# FPGA_SPI.net
KiCad netlist of a schematic drawn in Altium Designer
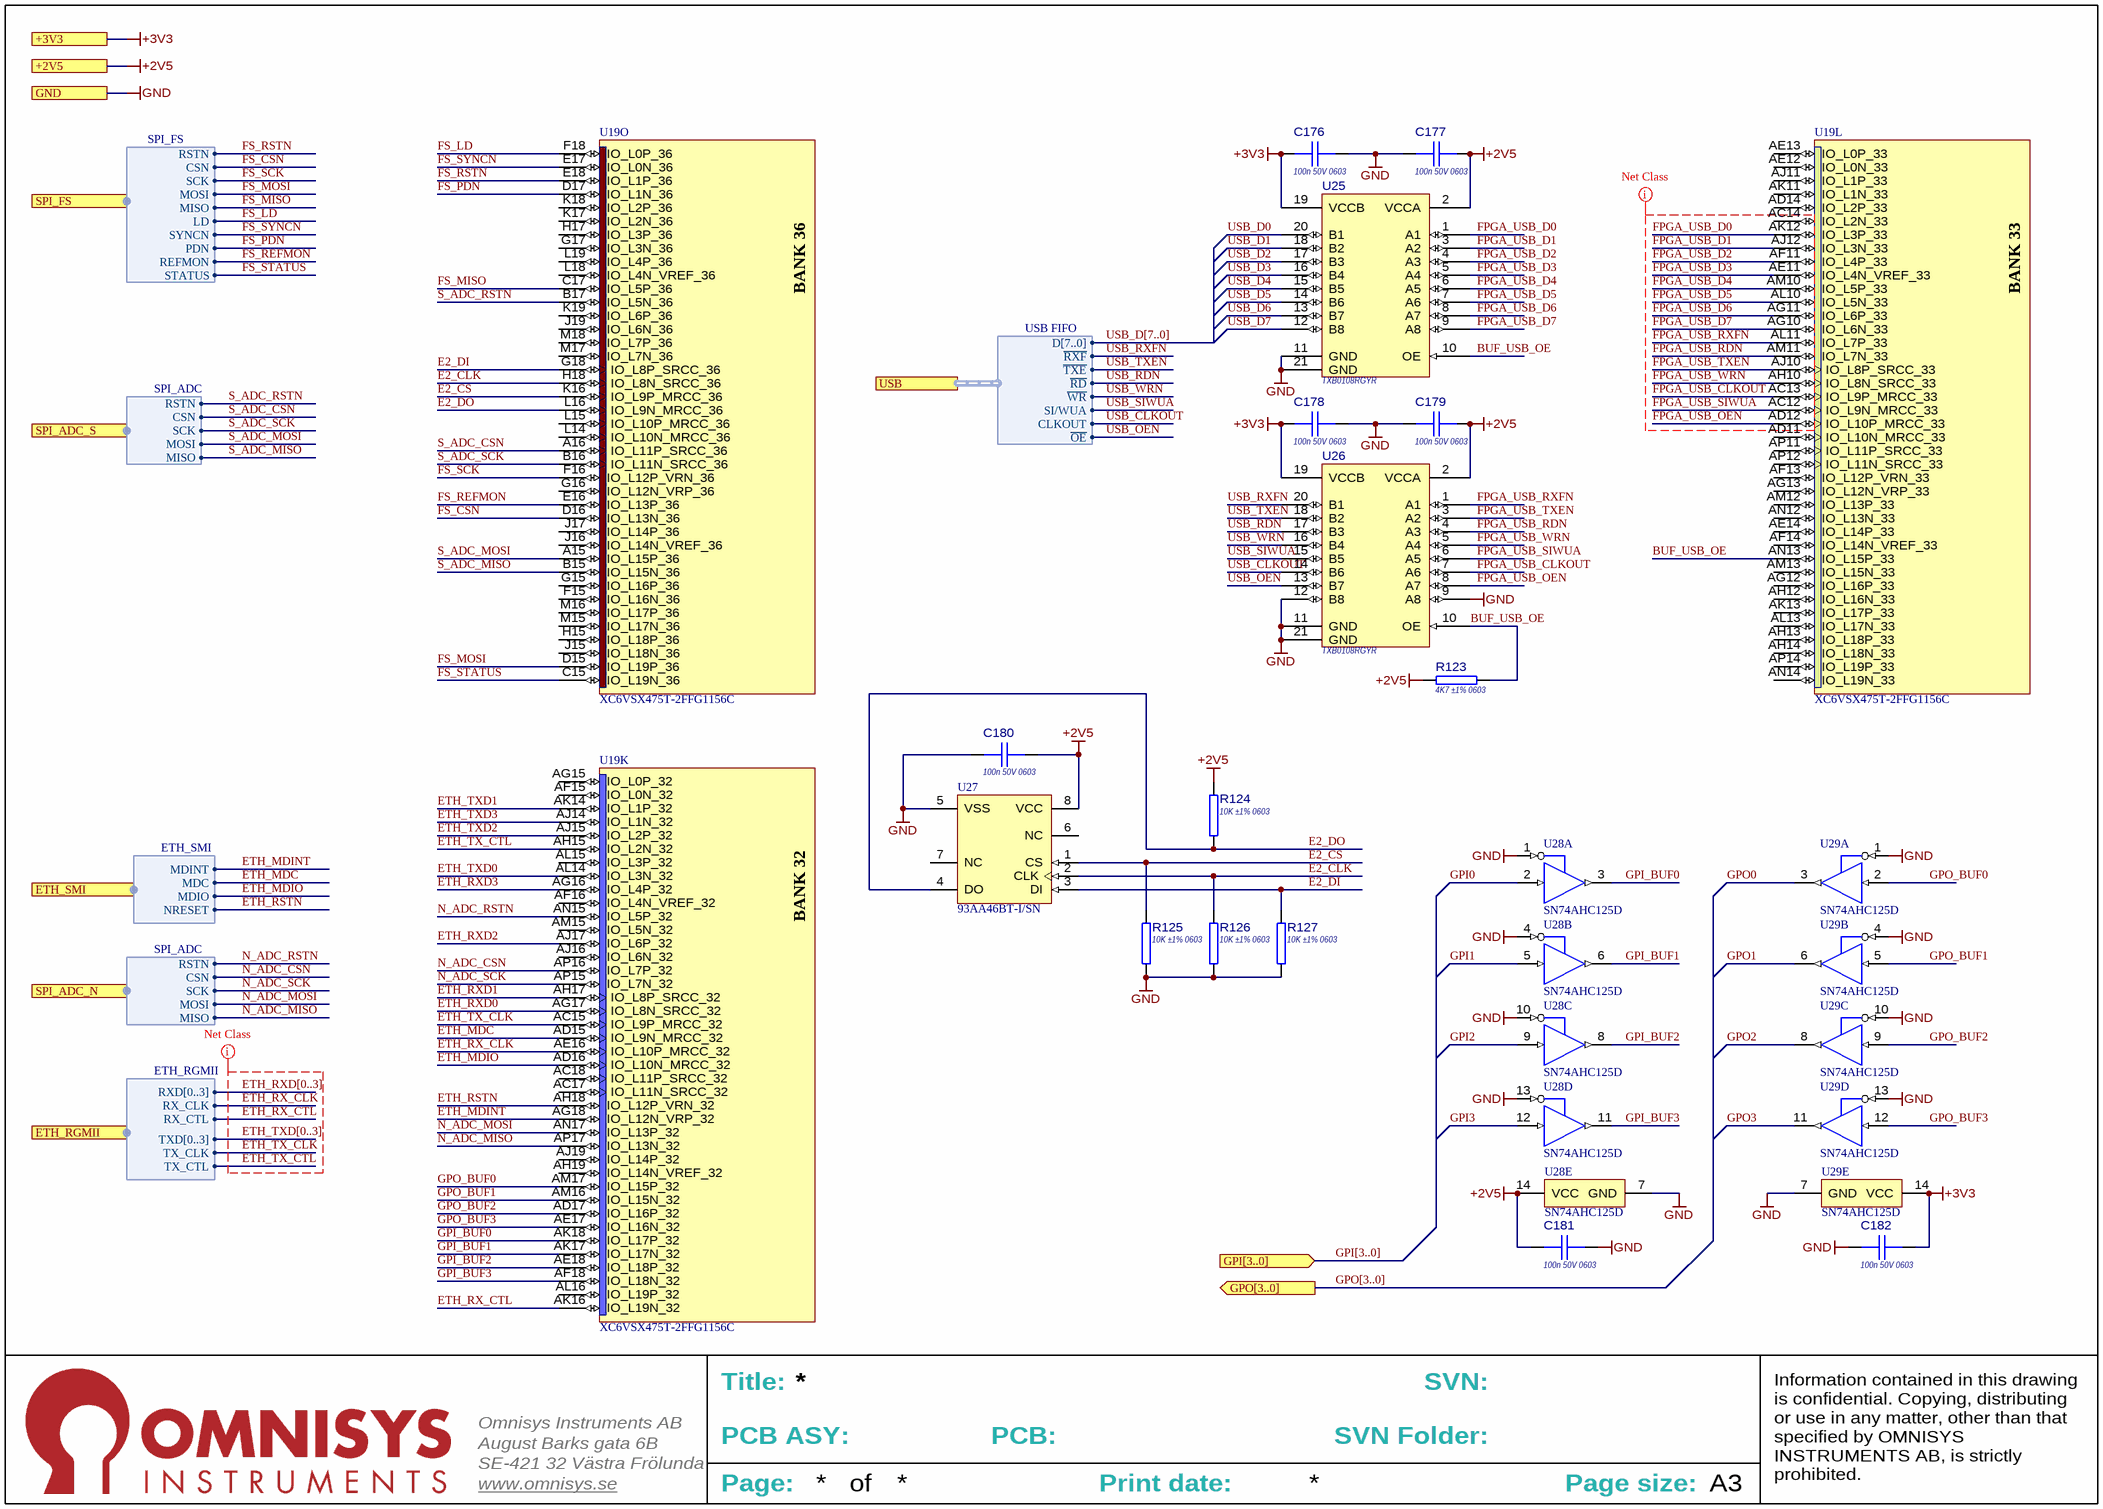
[diagram p0: FPGA_SPI.SchDoc]

(export (version "E")
  (design (tool "Eeschema 10.0.6"))
  (components
    (comp (ref "C176")
      (value "100n 50V 0603")
      (footprint "CAPC1608X90N")
      (description "100n 50V X7R ±10% 0603 (1608 metric)")
      (fields (field (name "PARTNUMBER") "GRM188R71H104KA93") (field (name "TOLERANCE") "±10%"))
      (libsource (lib "Omnisys Vault") (part "CAP-2PIN"))
    )
    (comp (ref "C177")
      (value "100n 50V 0603")
      (footprint "CAPC1608X90N")
      (description "100n 50V X7R ±10% 0603 (1608 metric)")
      (fields (field (name "PARTNUMBER") "GRM188R71H104KA93") (field (name "TOLERANCE") "±10%"))
      (libsource (lib "Omnisys Vault") (part "CAP-2PIN"))
    )
    (comp (ref "C178")
      (value "100n 50V 0603")
      (footprint "CAPC1608X90N")
      (description "100n 50V X7R ±10% 0603 (1608 metric)")
      (fields (field (name "PARTNUMBER") "GRM188R71H104KA93") (field (name "TOLERANCE") "±10%"))
      (libsource (lib "Omnisys Vault") (part "CAP-2PIN"))
    )
    (comp (ref "C179")
      (value "100n 50V 0603")
      (footprint "CAPC1608X90N")
      (description "100n 50V X7R ±10% 0603 (1608 metric)")
      (fields (field (name "PARTNUMBER") "GRM188R71H104KA93") (field (name "TOLERANCE") "±10%"))
      (libsource (lib "Omnisys Vault") (part "CAP-2PIN"))
    )
    (comp (ref "C180")
      (value "100n 50V 0603")
      (footprint "CAPC1608X90N")
      (description "100n 50V X7R ±10% 0603 (1608 metric)")
      (fields (field (name "PARTNUMBER") "GRM188R71H104KA93") (field (name "TOLERANCE") "±10%"))
      (libsource (lib "Omnisys Vault") (part "CAP-2PIN"))
    )
    (comp (ref "C181")
      (value "100n 50V 0603")
      (footprint "CAPC1608X90N")
      (description "100n 50V X7R ±10% 0603 (1608 metric)")
      (fields (field (name "PARTNUMBER") "GRM188R71H104KA93") (field (name "TOLERANCE") "±10%"))
      (libsource (lib "Omnisys Vault") (part "CAP-2PIN"))
    )
    (comp (ref "C182")
      (value "100n 50V 0603")
      (footprint "CAPC1608X90N")
      (description "100n 50V X7R ±10% 0603 (1608 metric)")
      (fields (field (name "PARTNUMBER") "GRM188R71H104KA93") (field (name "TOLERANCE") "±10%"))
      (libsource (lib "Omnisys Vault") (part "CAP-2PIN"))
    )
    (comp (ref "R123")
      (value "4K7 ±1% 0603")
      (footprint "RESC1608N")
      (description "4K7 ±1% ±100 ppm/˚C 0.10W 75V 0603 (1608 metric)")
      (fields (field (name "POWER") "100mW") (field (name "TOLERANCE") "1%"))
      (libsource (lib "Omnisys Vault") (part "RES-2PIN"))
    )
    (comp (ref "R124")
      (value "10K ±1% 0603")
      (footprint "RESC1608N")
      (description "10K ±1% ±100 ppm/˚C 0.10W 75V 0603 (1608 metric)")
      (fields (field (name "POWER") "100mW") (field (name "TOLERANCE") "1%"))
      (libsource (lib "Omnisys Vault") (part "RES-2PIN"))
    )
    (comp (ref "R125")
      (value "10K ±1% 0603")
      (footprint "RESC1608N")
      (description "10K ±1% ±100 ppm/˚C 0.10W 75V 0603 (1608 metric)")
      (fields (field (name "POWER") "100mW") (field (name "TOLERANCE") "1%"))
      (libsource (lib "Omnisys Vault") (part "RES-2PIN"))
    )
    (comp (ref "R126")
      (value "10K ±1% 0603")
      (footprint "RESC1608N")
      (description "10K ±1% ±100 ppm/˚C 0.10W 75V 0603 (1608 metric)")
      (fields (field (name "POWER") "100mW") (field (name "TOLERANCE") "1%"))
      (libsource (lib "Omnisys Vault") (part "RES-2PIN"))
    )
    (comp (ref "R127")
      (value "10K ±1% 0603")
      (footprint "RESC1608N")
      (description "10K ±1% ±100 ppm/˚C 0.10W 75V 0603 (1608 metric)")
      (fields (field (name "POWER") "100mW") (field (name "TOLERANCE") "1%"))
      (libsource (lib "Omnisys Vault") (part "RES-2PIN"))
    )
    (comp (ref "U19")
      (value "XC6VSX475T-2FFG1156C")
      (footprint "FFG1156")
      (libsource (lib "Altium Content Vault") (part "FPGA-XVR6-XC6VXXXXXT-GA1156"))
    )
    (comp (ref "U25")
      (value "TXB0108RGYR")
      (footprint "TXB0108RGYR")
      (description "TEXAS INSTRUMENTS   TXB0108RGYR   TRANSLATOR, VOLTAGE, 8BIT, 20VQFN")
      (libsource (lib "Omnisys Vault") (part "TXB0108RGYR"))
    )
    (comp (ref "U26")
      (value "TXB0108RGYR")
      (footprint "TXB0108RGYR")
      (description "TEXAS INSTRUMENTS   TXB0108RGYR   TRANSLATOR, VOLTAGE, 8BIT, 20VQFN")
      (libsource (lib "Omnisys Vault") (part "TXB0108RGYR"))
    )
    (comp (ref "U27")
      (value "93AA46BT-I/SN")
      (footprint "SOIC-SN8_L")
      (libsource (lib "Altium Content Vault") (part "MEM-SEEPROM-93AA46B-P-8"))
    )
    (comp (ref "U28")
      (value "SN74AHC125D")
      (footprint "SOIC127P600X175-14N")
      (description "Buffer/Line Driver 4-CH Non-Inverting 3-ST CMOS 14-Pin SOIC Tube")
      (libsource (lib "") (part "SN74AHC125D_1"))
    )
    (comp (ref "U29")
      (value "SN74AHC125D")
      (footprint "SOIC127P600X175-14L")
      (description "Buffer/Line Driver 4-CH Non-Inverting 3-ST CMOS 14-Pin SOIC Tube")
      (libsource (lib "Omnisys Vault") (part "SN74AHC125D"))
    )
  )
  (nets
    (net (code "7") (name "+2V5") (class "Default")
      (node (ref "C177") (pin "2") (pinfunction "2_2") (pintype "passive"))
      (node (ref "C179") (pin "2") (pinfunction "2_2") (pintype "passive"))
      (node (ref "C180") (pin "2") (pinfunction "2_2") (pintype "passive"))
      (node (ref "C181") (pin "1") (pinfunction "1_1") (pintype "passive"))
      (node (ref "R123") (pin "2") (pinfunction "2_2") (pintype "passive"))
      (node (ref "R124") (pin "2") (pinfunction "2_2") (pintype "passive"))
      (node (ref "U25") (pin "2") (pinfunction "VCCA_2") (pintype "power_in"))
      (node (ref "U26") (pin "2") (pinfunction "VCCA_2") (pintype "power_in"))
      (node (ref "U27") (pin "8") (pinfunction "VCC_8") (pintype "power_in"))
      (node (ref "U28") (pin "14") (pinfunction "VCC_14") (pintype "power_in"))
    )
    (net (code "8") (name "+3V3") (class "Default")
      (node (ref "C176") (pin "1") (pinfunction "1_1") (pintype "passive"))
      (node (ref "C178") (pin "1") (pinfunction "1_1") (pintype "passive"))
      (node (ref "C182") (pin "1") (pinfunction "1_1") (pintype "passive"))
      (node (ref "U25") (pin "19") (pinfunction "VCCB_19") (pintype "power_in"))
      (node (ref "U26") (pin "19") (pinfunction "VCCB_19") (pintype "power_in"))
      (node (ref "U29") (pin "14") (pinfunction "VCC_14") (pintype "power_in"))
    )
    (net (code "9") (name "/BUF_USB_OE") (class "Default")
      (node (ref "R123") (pin "1") (pinfunction "1_1") (pintype "passive"))
      (node (ref "U19") (pin "AN13") (pinfunction "IO_L15P_33_AN13") (pintype "bidirectional"))
      (node (ref "U25") (pin "10") (pinfunction "OE_10") (pintype "input"))
      (node (ref "U26") (pin "10") (pinfunction "OE_10") (pintype "input"))
    )
    (net (code "10") (name "/E2_CLK") (class "Default")
      (node (ref "R126") (pin "2") (pinfunction "2_2") (pintype "passive"))
      (node (ref "U19") (pin "H18") (pinfunction "IO_L8N_SRCC_36_H18") (pintype "bidirectional"))
      (node (ref "U27") (pin "2") (pinfunction "CLK_2") (pintype "input"))
    )
    (net (code "11") (name "/E2_CS") (class "Default")
      (node (ref "R125") (pin "2") (pinfunction "2_2") (pintype "passive"))
      (node (ref "U19") (pin "K16") (pinfunction "IO_L9P_MRCC_36_K16") (pintype "bidirectional"))
      (node (ref "U27") (pin "1") (pinfunction "CS_1") (pintype "input"))
    )
    (net (code "12") (name "/E2_DI") (class "Default")
      (node (ref "R127") (pin "2") (pinfunction "2_2") (pintype "passive"))
      (node (ref "U19") (pin "G18") (pinfunction "IO_L8P_SRCC_36_G18") (pintype "bidirectional"))
      (node (ref "U27") (pin "3") (pinfunction "DI_3") (pintype "input"))
    )
    (net (code "13") (name "/E2_DO") (class "Default")
      (node (ref "R124") (pin "1") (pinfunction "1_1") (pintype "passive"))
      (node (ref "U19") (pin "L16") (pinfunction "IO_L9N_MRCC_36_L16") (pintype "bidirectional"))
      (node (ref "U27") (pin "4") (pinfunction "DO_4") (pintype "tri_state"))
    )
    (net (code "14") (name "/ETH_MDC") (class "Default")
      (node (ref "U19") (pin "AD15") (pinfunction "IO_L9N_MRCC_32_AD15") (pintype "bidirectional"))
    )
    (net (code "15") (name "/ETH_MDINT") (class "Default")
      (node (ref "U19") (pin "AG18") (pinfunction "IO_L12N_VRP_32_AG18") (pintype "bidirectional"))
    )
    (net (code "16") (name "/ETH_MDIO") (class "Default")
      (node (ref "U19") (pin "AD16") (pinfunction "IO_L10N_MRCC_32_AD16") (pintype "bidirectional"))
    )
    (net (code "18") (name "/ETH_RSTN") (class "Default")
      (node (ref "U19") (pin "AH18") (pinfunction "IO_L12P_VRN_32_AH18") (pintype "bidirectional"))
    )
    (net (code "19") (name "/ETH_RXD0") (class "Default")
      (node (ref "U19") (pin "AG17") (pinfunction "IO_L8N_SRCC_32_AG17") (pintype "bidirectional"))
    )
    (net (code "20") (name "/ETH_RXD1") (class "Default")
      (node (ref "U19") (pin "AH17") (pinfunction "IO_L8P_SRCC_32_AH17") (pintype "bidirectional"))
    )
    (net (code "21") (name "/ETH_RXD2") (class "Default")
      (node (ref "U19") (pin "AJ17") (pinfunction "IO_L6P_32_AJ17") (pintype "bidirectional"))
    )
    (net (code "22") (name "/ETH_RXD3") (class "Default")
      (node (ref "U19") (pin "AG16") (pinfunction "IO_L4P_32_AG16") (pintype "bidirectional"))
    )
    (net (code "24") (name "/ETH_RX_CLK") (class "Default")
      (node (ref "U19") (pin "AE16") (pinfunction "IO_L10P_MRCC_32_AE16") (pintype "bidirectional"))
    )
    (net (code "25") (name "/ETH_RX_CTL") (class "Default")
      (node (ref "U19") (pin "AK16") (pinfunction "IO_L19N_32_AK16") (pintype "bidirectional"))
    )
    (net (code "26") (name "/ETH_TXD0") (class "Default")
      (node (ref "U19") (pin "AL14") (pinfunction "IO_L3N_32_AL14") (pintype "bidirectional"))
    )
    (net (code "27") (name "/ETH_TXD1") (class "Default")
      (node (ref "U19") (pin "AK14") (pinfunction "IO_L1P_32_AK14") (pintype "bidirectional"))
    )
    (net (code "28") (name "/ETH_TXD2") (class "Default")
      (node (ref "U19") (pin "AJ15") (pinfunction "IO_L2P_32_AJ15") (pintype "bidirectional"))
    )
    (net (code "29") (name "/ETH_TXD3") (class "Default")
      (node (ref "U19") (pin "AJ14") (pinfunction "IO_L1N_32_AJ14") (pintype "bidirectional"))
    )
    (net (code "30") (name "/ETH_TX_CLK") (class "Default")
      (node (ref "U19") (pin "AC15") (pinfunction "IO_L9P_MRCC_32_AC15") (pintype "bidirectional"))
    )
    (net (code "31") (name "/ETH_TX_CTL") (class "Default")
      (node (ref "U19") (pin "AH15") (pinfunction "IO_L2N_32_AH15") (pintype "bidirectional"))
    )
    (net (code "32") (name "/FPGA_USB_CLKOUT") (class "Default")
      (node (ref "U19") (pin "AC13") (pinfunction "IO_L9P_MRCC_33_AC13") (pintype "bidirectional"))
      (node (ref "U26") (pin "7") (pinfunction "A6_7") (pintype "bidirectional"))
    )
    (net (code "33") (name "/FPGA_USB_D0") (class "Default")
      (node (ref "U19") (pin "AK12") (pinfunction "IO_L3P_33_AK12") (pintype "bidirectional"))
      (node (ref "U25") (pin "1") (pinfunction "A1_1") (pintype "bidirectional"))
    )
    (net (code "34") (name "/FPGA_USB_D1") (class "Default")
      (node (ref "U19") (pin "AJ12") (pinfunction "IO_L3N_33_AJ12") (pintype "bidirectional"))
      (node (ref "U25") (pin "3") (pinfunction "A2_3") (pintype "bidirectional"))
    )
    (net (code "35") (name "/FPGA_USB_D2") (class "Default")
      (node (ref "U19") (pin "AF11") (pinfunction "IO_L4P_33_AF11") (pintype "bidirectional"))
      (node (ref "U25") (pin "4") (pinfunction "A3_4") (pintype "bidirectional"))
    )
    (net (code "36") (name "/FPGA_USB_D3") (class "Default")
      (node (ref "U19") (pin "AE11") (pinfunction "IO_L4N_VREF_33_AE11") (pintype "bidirectional"))
      (node (ref "U25") (pin "5") (pinfunction "A4_5") (pintype "bidirectional"))
    )
    (net (code "37") (name "/FPGA_USB_D4") (class "Default")
      (node (ref "U19") (pin "AM10") (pinfunction "IO_L5P_33_AM10") (pintype "bidirectional"))
      (node (ref "U25") (pin "6") (pinfunction "A5_6") (pintype "bidirectional"))
    )
    (net (code "38") (name "/FPGA_USB_D5") (class "Default")
      (node (ref "U19") (pin "AL10") (pinfunction "IO_L5N_33_AL10") (pintype "bidirectional"))
      (node (ref "U25") (pin "7") (pinfunction "A6_7") (pintype "bidirectional"))
    )
    (net (code "39") (name "/FPGA_USB_D6") (class "Default")
      (node (ref "U19") (pin "AG11") (pinfunction "IO_L6P_33_AG11") (pintype "bidirectional"))
      (node (ref "U25") (pin "8") (pinfunction "A7_8") (pintype "bidirectional"))
    )
    (net (code "40") (name "/FPGA_USB_D7") (class "Default")
      (node (ref "U19") (pin "AG10") (pinfunction "IO_L6N_33_AG10") (pintype "bidirectional"))
      (node (ref "U25") (pin "9") (pinfunction "A8_9") (pintype "bidirectional"))
    )
    (net (code "41") (name "/FPGA_USB_OEN") (class "Default")
      (node (ref "U19") (pin "AD12") (pinfunction "IO_L10P_MRCC_33_AD12") (pintype "bidirectional"))
      (node (ref "U26") (pin "8") (pinfunction "A7_8") (pintype "bidirectional"))
    )
    (net (code "42") (name "/FPGA_USB_RDN") (class "Default")
      (node (ref "U19") (pin "AM11") (pinfunction "IO_L7N_33_AM11") (pintype "bidirectional"))
      (node (ref "U26") (pin "4") (pinfunction "A3_4") (pintype "bidirectional"))
    )
    (net (code "43") (name "/FPGA_USB_RXFN") (class "Default")
      (node (ref "U19") (pin "AL11") (pinfunction "IO_L7P_33_AL11") (pintype "bidirectional"))
      (node (ref "U26") (pin "1") (pinfunction "A1_1") (pintype "bidirectional"))
    )
    (net (code "44") (name "/FPGA_USB_SIWUA") (class "Default")
      (node (ref "U19") (pin "AC12") (pinfunction "IO_L9N_MRCC_33_AC12") (pintype "bidirectional"))
      (node (ref "U26") (pin "6") (pinfunction "A5_6") (pintype "bidirectional"))
    )
    (net (code "45") (name "/FPGA_USB_TXEN") (class "Default")
      (node (ref "U19") (pin "AJ10") (pinfunction "IO_L8P_SRCC_33_AJ10") (pintype "bidirectional"))
      (node (ref "U26") (pin "3") (pinfunction "A2_3") (pintype "bidirectional"))
    )
    (net (code "46") (name "/FPGA_USB_WRN") (class "Default")
      (node (ref "U19") (pin "AH10") (pinfunction "IO_L8N_SRCC_33_AH10") (pintype "bidirectional"))
      (node (ref "U26") (pin "5") (pinfunction "A4_5") (pintype "bidirectional"))
    )
    (net (code "47") (name "/FS_CSN") (class "Default")
      (node (ref "U19") (pin "D16") (pinfunction "IO_L13N_36_D16") (pintype "bidirectional"))
    )
    (net (code "48") (name "/FS_LD") (class "Default")
      (node (ref "U19") (pin "F18") (pinfunction "IO_L0P_36_F18") (pintype "bidirectional"))
    )
    (net (code "49") (name "/FS_MISO") (class "Default")
      (node (ref "U19") (pin "C17") (pinfunction "IO_L5P_36_C17") (pintype "bidirectional"))
    )
    (net (code "50") (name "/FS_MOSI") (class "Default")
      (node (ref "U19") (pin "D15") (pinfunction "IO_L19P_36_D15") (pintype "bidirectional"))
    )
    (net (code "51") (name "/FS_PDN") (class "Default")
      (node (ref "U19") (pin "D17") (pinfunction "IO_L1N_36_D17") (pintype "bidirectional"))
    )
    (net (code "52") (name "/FS_REFMON") (class "Default")
      (node (ref "U19") (pin "E16") (pinfunction "IO_L13P_36_E16") (pintype "bidirectional"))
    )
    (net (code "53") (name "/FS_RSTN") (class "Default")
      (node (ref "U19") (pin "E18") (pinfunction "IO_L1P_36_E18") (pintype "bidirectional"))
    )
    (net (code "54") (name "/FS_SCK") (class "Default")
      (node (ref "U19") (pin "F16") (pinfunction "IO_L12P_VRN_36_F16") (pintype "bidirectional"))
    )
    (net (code "55") (name "/FS_STATUS") (class "Default")
      (node (ref "U19") (pin "C15") (pinfunction "IO_L19N_36_C15") (pintype "bidirectional"))
    )
    (net (code "56") (name "/FS_SYNCN") (class "Default")
      (node (ref "U19") (pin "E17") (pinfunction "IO_L0N_36_E17") (pintype "bidirectional"))
    )
    (net (code "57") (name "/GPI0") (class "Default")
      (node (ref "U28") (pin "2") (pinfunction "1A_2") (pintype "input"))
    )
    (net (code "58") (name "/GPI1") (class "Default")
      (node (ref "U28") (pin "5") (pinfunction "2A_5") (pintype "input"))
    )
    (net (code "59") (name "/GPI2") (class "Default")
      (node (ref "U28") (pin "9") (pinfunction "3A_9") (pintype "input"))
    )
    (net (code "60") (name "/GPI3") (class "Default")
      (node (ref "U28") (pin "12") (pinfunction "4A_12") (pintype "input"))
    )
    (net (code "62") (name "/GPI_BUF0") (class "Default")
      (node (ref "U19") (pin "AK18") (pinfunction "IO_L17P_32_AK18") (pintype "bidirectional"))
      (node (ref "U28") (pin "3") (pinfunction "1Y_3") (pintype "output"))
    )
    (net (code "63") (name "/GPI_BUF1") (class "Default")
      (node (ref "U19") (pin "AK17") (pinfunction "IO_L17N_32_AK17") (pintype "bidirectional"))
      (node (ref "U28") (pin "6") (pinfunction "2Y_6") (pintype "output"))
    )
    (net (code "64") (name "/GPI_BUF2") (class "Default")
      (node (ref "U19") (pin "AE18") (pinfunction "IO_L18P_32_AE18") (pintype "bidirectional"))
      (node (ref "U28") (pin "8") (pinfunction "3Y_8") (pintype "output"))
    )
    (net (code "65") (name "/GPI_BUF3") (class "Default")
      (node (ref "U19") (pin "AF18") (pinfunction "IO_L18N_32_AF18") (pintype "bidirectional"))
      (node (ref "U28") (pin "11") (pinfunction "4Y_11") (pintype "output"))
    )
    (net (code "66") (name "/GPO0") (class "Default")
      (node (ref "U29") (pin "3") (pinfunction "1Y_3") (pintype "output"))
    )
    (net (code "67") (name "/GPO1") (class "Default")
      (node (ref "U29") (pin "6") (pinfunction "2Y_6") (pintype "output"))
    )
    (net (code "68") (name "/GPO2") (class "Default")
      (node (ref "U29") (pin "8") (pinfunction "3Y_8") (pintype "output"))
    )
    (net (code "69") (name "/GPO3") (class "Default")
      (node (ref "U29") (pin "11") (pinfunction "4Y_11") (pintype "output"))
    )
    (net (code "71") (name "/GPO_BUF0") (class "Default")
      (node (ref "U19") (pin "AM17") (pinfunction "IO_L15P_32_AM17") (pintype "bidirectional"))
      (node (ref "U29") (pin "2") (pinfunction "1A_2") (pintype "input"))
    )
    (net (code "72") (name "/GPO_BUF1") (class "Default")
      (node (ref "U19") (pin "AM16") (pinfunction "IO_L15N_32_AM16") (pintype "bidirectional"))
      (node (ref "U29") (pin "5") (pinfunction "2A_5") (pintype "input"))
    )
    (net (code "73") (name "/GPO_BUF2") (class "Default")
      (node (ref "U19") (pin "AD17") (pinfunction "IO_L16P_32_AD17") (pintype "bidirectional"))
      (node (ref "U29") (pin "9") (pinfunction "3A_9") (pintype "input"))
    )
    (net (code "74") (name "/GPO_BUF3") (class "Default")
      (node (ref "U19") (pin "AE17") (pinfunction "IO_L16N_32_AE17") (pintype "bidirectional"))
      (node (ref "U29") (pin "12") (pinfunction "4A_12") (pintype "input"))
    )
    (net (code "75") (name "/N_ADC_CSN") (class "Default")
      (node (ref "U19") (pin "AP16") (pinfunction "IO_L7P_32_AP16") (pintype "bidirectional"))
    )
    (net (code "76") (name "/N_ADC_MISO") (class "Default")
      (node (ref "U19") (pin "AP17") (pinfunction "IO_L13N_32_AP17") (pintype "bidirectional"))
    )
    (net (code "77") (name "/N_ADC_MOSI") (class "Default")
      (node (ref "U19") (pin "AN17") (pinfunction "IO_L13P_32_AN17") (pintype "bidirectional"))
    )
    (net (code "78") (name "/N_ADC_RSTN") (class "Default")
      (node (ref "U19") (pin "AN15") (pinfunction "IO_L5P_32_AN15") (pintype "bidirectional"))
    )
    (net (code "79") (name "/N_ADC_SCK") (class "Default")
      (node (ref "U19") (pin "AP15") (pinfunction "IO_L7N_32_AP15") (pintype "bidirectional"))
    )
    (net (code "80") (name "/S_ADC_CSN") (class "Default")
      (node (ref "U19") (pin "A16") (pinfunction "IO_L11P_SRCC_36_A16") (pintype "bidirectional"))
    )
    (net (code "81") (name "/S_ADC_MISO") (class "Default")
      (node (ref "U19") (pin "B15") (pinfunction "IO_L15N_36_B15") (pintype "bidirectional"))
    )
    (net (code "82") (name "/S_ADC_MOSI") (class "Default")
      (node (ref "U19") (pin "A15") (pinfunction "IO_L15P_36_A15") (pintype "bidirectional"))
    )
    (net (code "83") (name "/S_ADC_RSTN") (class "Default")
      (node (ref "U19") (pin "B17") (pinfunction "IO_L5N_36_B17") (pintype "bidirectional"))
    )
    (net (code "84") (name "/S_ADC_SCK") (class "Default")
      (node (ref "U19") (pin "B16") (pinfunction "IO_L11N_SRCC_36_B16") (pintype "bidirectional"))
    )
    (net (code "85") (name "/USB_CLKOUT") (class "Default")
      (node (ref "U26") (pin "14") (pinfunction "B6_14") (pintype "bidirectional"))
    )
    (net (code "86") (name "/USB_D0") (class "Default")
      (node (ref "U25") (pin "20") (pinfunction "B1_20") (pintype "bidirectional"))
    )
    (net (code "87") (name "/USB_D1") (class "Default")
      (node (ref "U25") (pin "18") (pinfunction "B2_18") (pintype "bidirectional"))
    )
    (net (code "88") (name "/USB_D2") (class "Default")
      (node (ref "U25") (pin "17") (pinfunction "B3_17") (pintype "bidirectional"))
    )
    (net (code "89") (name "/USB_D3") (class "Default")
      (node (ref "U25") (pin "16") (pinfunction "B4_16") (pintype "bidirectional"))
    )
    (net (code "90") (name "/USB_D4") (class "Default")
      (node (ref "U25") (pin "15") (pinfunction "B5_15") (pintype "bidirectional"))
    )
    (net (code "91") (name "/USB_D5") (class "Default")
      (node (ref "U25") (pin "14") (pinfunction "B6_14") (pintype "bidirectional"))
    )
    (net (code "92") (name "/USB_D6") (class "Default")
      (node (ref "U25") (pin "13") (pinfunction "B7_13") (pintype "bidirectional"))
    )
    (net (code "93") (name "/USB_D7") (class "Default")
      (node (ref "U25") (pin "12") (pinfunction "B8_12") (pintype "bidirectional"))
    )
    (net (code "95") (name "/USB_OEN") (class "Default")
      (node (ref "U26") (pin "13") (pinfunction "B7_13") (pintype "bidirectional"))
    )
    (net (code "96") (name "/USB_RDN") (class "Default")
      (node (ref "U26") (pin "17") (pinfunction "B3_17") (pintype "bidirectional"))
    )
    (net (code "97") (name "/USB_RXFN") (class "Default")
      (node (ref "U26") (pin "20") (pinfunction "B1_20") (pintype "bidirectional"))
    )
    (net (code "98") (name "/USB_SIWUA") (class "Default")
      (node (ref "U26") (pin "15") (pinfunction "B5_15") (pintype "bidirectional"))
    )
    (net (code "99") (name "/USB_TXEN") (class "Default")
      (node (ref "U26") (pin "18") (pinfunction "B2_18") (pintype "bidirectional"))
    )
    (net (code "100") (name "/USB_WRN") (class "Default")
      (node (ref "U26") (pin "16") (pinfunction "B4_16") (pintype "bidirectional"))
    )
    (net (code "106") (name "GND") (class "Default")
      (node (ref "C176") (pin "2") (pinfunction "2_2") (pintype "passive"))
      (node (ref "C177") (pin "1") (pinfunction "1_1") (pintype "passive"))
      (node (ref "C178") (pin "2") (pinfunction "2_2") (pintype "passive"))
      (node (ref "C179") (pin "1") (pinfunction "1_1") (pintype "passive"))
      (node (ref "C180") (pin "1") (pinfunction "1_1") (pintype "passive"))
      (node (ref "C181") (pin "2") (pinfunction "2_2") (pintype "passive"))
      (node (ref "C182") (pin "2") (pinfunction "2_2") (pintype "passive"))
      (node (ref "R125") (pin "1") (pinfunction "1_1") (pintype "passive"))
      (node (ref "R126") (pin "1") (pinfunction "1_1") (pintype "passive"))
      (node (ref "R127") (pin "1") (pinfunction "1_1") (pintype "passive"))
      (node (ref "U25") (pin "11") (pinfunction "GND_11") (pintype "power_in"))
      (node (ref "U25") (pin "21") (pinfunction "GND_21") (pintype "power_in"))
      (node (ref "U26") (pin "11") (pinfunction "GND_11") (pintype "power_in"))
      (node (ref "U26") (pin "12") (pinfunction "B8_12") (pintype "bidirectional"))
      (node (ref "U26") (pin "21") (pinfunction "GND_21") (pintype "power_in"))
      (node (ref "U26") (pin "9") (pinfunction "A8_9") (pintype "bidirectional"))
      (node (ref "U27") (pin "5") (pinfunction "VSS_5") (pintype "power_in"))
      (node (ref "U28") (pin "1") (pinfunction "1OE#_1") (pintype "input"))
      (node (ref "U28") (pin "10") (pinfunction "3OE#_10") (pintype "input"))
      (node (ref "U28") (pin "13") (pinfunction "4OE#_13") (pintype "input"))
      (node (ref "U28") (pin "4") (pinfunction "2OE#_4") (pintype "input"))
      (node (ref "U28") (pin "7") (pinfunction "GND_7") (pintype "power_in"))
      (node (ref "U29") (pin "1") (pinfunction "1OE#_1") (pintype "input"))
      (node (ref "U29") (pin "10") (pinfunction "3OE#_10") (pintype "input"))
      (node (ref "U29") (pin "13") (pinfunction "4OE#_13") (pintype "input"))
      (node (ref "U29") (pin "4") (pinfunction "2OE#_4") (pintype "input"))
      (node (ref "U29") (pin "7") (pinfunction "GND_7") (pintype "power_in"))
    )
    (net (code "107") (name "unconnected-(U19K-IO_L0N_32-PadAF15)") (class "Default")
      (node (ref "U19") (pin "AF15") (pinfunction "IO_L0N_32_AF15") (pintype "bidirectional"))
    )
    (net (code "108") (name "unconnected-(U19K-IO_L0P_32-PadAG15)") (class "Default")
      (node (ref "U19") (pin "AG15") (pinfunction "IO_L0P_32_AG15") (pintype "bidirectional"))
    )
    (net (code "109") (name "unconnected-(U19K-IO_L3P_32-PadAL15)") (class "Default")
      (node (ref "U19") (pin "AL15") (pinfunction "IO_L3P_32_AL15") (pintype "bidirectional"))
    )
    (net (code "110") (name "unconnected-(U19K-IO_L4N_VREF_32-PadAF16)") (class "Default")
      (node (ref "U19") (pin "AF16") (pinfunction "IO_L4N_VREF_32_AF16") (pintype "bidirectional"))
    )
    (net (code "111") (name "unconnected-(U19K-IO_L5N_32-PadAM15)") (class "Default")
      (node (ref "U19") (pin "AM15") (pinfunction "IO_L5N_32_AM15") (pintype "bidirectional"))
    )
    (net (code "112") (name "unconnected-(U19K-IO_L6N_32-PadAJ16)") (class "Default")
      (node (ref "U19") (pin "AJ16") (pinfunction "IO_L6N_32_AJ16") (pintype "bidirectional"))
    )
    (net (code "113") (name "unconnected-(U19K-IO_L11N_SRCC_32-PadAC17)") (class "Default")
      (node (ref "U19") (pin "AC17") (pinfunction "IO_L11N_SRCC_32_AC17") (pintype "bidirectional"))
    )
    (net (code "114") (name "unconnected-(U19K-IO_L11P_SRCC_32-PadAC18)") (class "Default")
      (node (ref "U19") (pin "AC18") (pinfunction "IO_L11P_SRCC_32_AC18") (pintype "bidirectional"))
    )
    (net (code "115") (name "unconnected-(U19K-IO_L14N_VREF_32-PadAH19)") (class "Default")
      (node (ref "U19") (pin "AH19") (pinfunction "IO_L14N_VREF_32_AH19") (pintype "bidirectional"))
    )
    (net (code "116") (name "unconnected-(U19K-IO_L14P_32-PadAJ19)") (class "Default")
      (node (ref "U19") (pin "AJ19") (pinfunction "IO_L14P_32_AJ19") (pintype "bidirectional"))
    )
    (net (code "117") (name "unconnected-(U19K-IO_L19P_32-PadAL16)") (class "Default")
      (node (ref "U19") (pin "AL16") (pinfunction "IO_L19P_32_AL16") (pintype "bidirectional"))
    )
    (net (code "118") (name "unconnected-(U19L-IO_L0N_33-PadAE12)") (class "Default")
      (node (ref "U19") (pin "AE12") (pinfunction "IO_L0N_33_AE12") (pintype "bidirectional"))
    )
    (net (code "119") (name "unconnected-(U19L-IO_L0P_33-PadAE13)") (class "Default")
      (node (ref "U19") (pin "AE13") (pinfunction "IO_L0P_33_AE13") (pintype "bidirectional"))
    )
    (net (code "120") (name "unconnected-(U19L-IO_L1N_33-PadAK11)") (class "Default")
      (node (ref "U19") (pin "AK11") (pinfunction "IO_L1N_33_AK11") (pintype "bidirectional"))
    )
    (net (code "121") (name "unconnected-(U19L-IO_L1P_33-PadAJ11)") (class "Default")
      (node (ref "U19") (pin "AJ11") (pinfunction "IO_L1P_33_AJ11") (pintype "bidirectional"))
    )
    (net (code "122") (name "unconnected-(U19L-IO_L2N_33-PadAC14)") (class "Default")
      (node (ref "U19") (pin "AC14") (pinfunction "IO_L2N_33_AC14") (pintype "bidirectional"))
    )
    (net (code "123") (name "unconnected-(U19L-IO_L2P_33-PadAD14)") (class "Default")
      (node (ref "U19") (pin "AD14") (pinfunction "IO_L2P_33_AD14") (pintype "bidirectional"))
    )
    (net (code "124") (name "unconnected-(U19L-IO_L10N_MRCC_33-PadAD11)") (class "Default")
      (node (ref "U19") (pin "AD11") (pinfunction "IO_L10N_MRCC_33_AD11") (pintype "bidirectional"))
    )
    (net (code "125") (name "unconnected-(U19L-IO_L11N_SRCC_33-PadAP12)") (class "Default")
      (node (ref "U19") (pin "AP12") (pinfunction "IO_L11N_SRCC_33_AP12") (pintype "bidirectional"))
    )
    (net (code "126") (name "unconnected-(U19L-IO_L11P_SRCC_33-PadAP11)") (class "Default")
      (node (ref "U19") (pin "AP11") (pinfunction "IO_L11P_SRCC_33_AP11") (pintype "bidirectional"))
    )
    (net (code "127") (name "unconnected-(U19L-IO_L12N_VRP_33-PadAG13)") (class "Default")
      (node (ref "U19") (pin "AG13") (pinfunction "IO_L12N_VRP_33_AG13") (pintype "bidirectional"))
    )
    (net (code "128") (name "unconnected-(U19L-IO_L12P_VRN_33-PadAF13)") (class "Default")
      (node (ref "U19") (pin "AF13") (pinfunction "IO_L12P_VRN_33_AF13") (pintype "bidirectional"))
    )
    (net (code "129") (name "unconnected-(U19L-IO_L13N_33-PadAN12)") (class "Default")
      (node (ref "U19") (pin "AN12") (pinfunction "IO_L13N_33_AN12") (pintype "bidirectional"))
    )
    (net (code "130") (name "unconnected-(U19L-IO_L13P_33-PadAM12)") (class "Default")
      (node (ref "U19") (pin "AM12") (pinfunction "IO_L13P_33_AM12") (pintype "bidirectional"))
    )
    (net (code "131") (name "unconnected-(U19L-IO_L14N_VREF_33-PadAF14)") (class "Default")
      (node (ref "U19") (pin "AF14") (pinfunction "IO_L14N_VREF_33_AF14") (pintype "bidirectional"))
    )
    (net (code "132") (name "unconnected-(U19L-IO_L14P_33-PadAE14)") (class "Default")
      (node (ref "U19") (pin "AE14") (pinfunction "IO_L14P_33_AE14") (pintype "bidirectional"))
    )
    (net (code "133") (name "unconnected-(U19L-IO_L15N_33-PadAM13)") (class "Default")
      (node (ref "U19") (pin "AM13") (pinfunction "IO_L15N_33_AM13") (pintype "bidirectional"))
    )
    (net (code "134") (name "unconnected-(U19L-IO_L16N_33-PadAH12)") (class "Default")
      (node (ref "U19") (pin "AH12") (pinfunction "IO_L16N_33_AH12") (pintype "bidirectional"))
    )
    (net (code "135") (name "unconnected-(U19L-IO_L16P_33-PadAG12)") (class "Default")
      (node (ref "U19") (pin "AG12") (pinfunction "IO_L16P_33_AG12") (pintype "bidirectional"))
    )
    (net (code "136") (name "unconnected-(U19L-IO_L17N_33-PadAL13)") (class "Default")
      (node (ref "U19") (pin "AL13") (pinfunction "IO_L17N_33_AL13") (pintype "bidirectional"))
    )
    (net (code "137") (name "unconnected-(U19L-IO_L17P_33-PadAK13)") (class "Default")
      (node (ref "U19") (pin "AK13") (pinfunction "IO_L17P_33_AK13") (pintype "bidirectional"))
    )
    (net (code "138") (name "unconnected-(U19L-IO_L18N_33-PadAH14)") (class "Default")
      (node (ref "U19") (pin "AH14") (pinfunction "IO_L18N_33_AH14") (pintype "bidirectional"))
    )
    (net (code "139") (name "unconnected-(U19L-IO_L18P_33-PadAH13)") (class "Default")
      (node (ref "U19") (pin "AH13") (pinfunction "IO_L18P_33_AH13") (pintype "bidirectional"))
    )
    (net (code "140") (name "unconnected-(U19L-IO_L19N_33-PadAN14)") (class "Default")
      (node (ref "U19") (pin "AN14") (pinfunction "IO_L19N_33_AN14") (pintype "bidirectional"))
    )
    (net (code "141") (name "unconnected-(U19L-IO_L19P_33-PadAP14)") (class "Default")
      (node (ref "U19") (pin "AP14") (pinfunction "IO_L19P_33_AP14") (pintype "bidirectional"))
    )
    (net (code "142") (name "unconnected-(U19O-IO_L2N_36-PadK17)") (class "Default")
      (node (ref "U19") (pin "K17") (pinfunction "IO_L2N_36_K17") (pintype "bidirectional"))
    )
    (net (code "143") (name "unconnected-(U19O-IO_L2P_36-PadK18)") (class "Default")
      (node (ref "U19") (pin "K18") (pinfunction "IO_L2P_36_K18") (pintype "bidirectional"))
    )
    (net (code "144") (name "unconnected-(U19O-IO_L3N_36-PadG17)") (class "Default")
      (node (ref "U19") (pin "G17") (pinfunction "IO_L3N_36_G17") (pintype "bidirectional"))
    )
    (net (code "145") (name "unconnected-(U19O-IO_L3P_36-PadH17)") (class "Default")
      (node (ref "U19") (pin "H17") (pinfunction "IO_L3P_36_H17") (pintype "bidirectional"))
    )
    (net (code "146") (name "unconnected-(U19O-IO_L4N_VREF_36-PadL18)") (class "Default")
      (node (ref "U19") (pin "L18") (pinfunction "IO_L4N_VREF_36_L18") (pintype "bidirectional"))
    )
    (net (code "147") (name "unconnected-(U19O-IO_L4P_36-PadL19)") (class "Default")
      (node (ref "U19") (pin "L19") (pinfunction "IO_L4P_36_L19") (pintype "bidirectional"))
    )
    (net (code "148") (name "unconnected-(U19O-IO_L6N_36-PadJ19)") (class "Default")
      (node (ref "U19") (pin "J19") (pinfunction "IO_L6N_36_J19") (pintype "bidirectional"))
    )
    (net (code "149") (name "unconnected-(U19O-IO_L6P_36-PadK19)") (class "Default")
      (node (ref "U19") (pin "K19") (pinfunction "IO_L6P_36_K19") (pintype "bidirectional"))
    )
    (net (code "150") (name "unconnected-(U19O-IO_L7N_36-PadM17)") (class "Default")
      (node (ref "U19") (pin "M17") (pinfunction "IO_L7N_36_M17") (pintype "bidirectional"))
    )
    (net (code "151") (name "unconnected-(U19O-IO_L7P_36-PadM18)") (class "Default")
      (node (ref "U19") (pin "M18") (pinfunction "IO_L7P_36_M18") (pintype "bidirectional"))
    )
    (net (code "152") (name "unconnected-(U19O-IO_L10N_MRCC_36-PadL14)") (class "Default")
      (node (ref "U19") (pin "L14") (pinfunction "IO_L10N_MRCC_36_L14") (pintype "bidirectional"))
    )
    (net (code "153") (name "unconnected-(U19O-IO_L10P_MRCC_36-PadL15)") (class "Default")
      (node (ref "U19") (pin "L15") (pinfunction "IO_L10P_MRCC_36_L15") (pintype "bidirectional"))
    )
    (net (code "154") (name "unconnected-(U19O-IO_L12N_VRP_36-PadG16)") (class "Default")
      (node (ref "U19") (pin "G16") (pinfunction "IO_L12N_VRP_36_G16") (pintype "bidirectional"))
    )
    (net (code "155") (name "unconnected-(U19O-IO_L14N_VREF_36-PadJ16)") (class "Default")
      (node (ref "U19") (pin "J16") (pinfunction "IO_L14N_VREF_36_J16") (pintype "bidirectional"))
    )
    (net (code "156") (name "unconnected-(U19O-IO_L14P_36-PadJ17)") (class "Default")
      (node (ref "U19") (pin "J17") (pinfunction "IO_L14P_36_J17") (pintype "bidirectional"))
    )
    (net (code "157") (name "unconnected-(U19O-IO_L16N_36-PadF15)") (class "Default")
      (node (ref "U19") (pin "F15") (pinfunction "IO_L16N_36_F15") (pintype "bidirectional"))
    )
    (net (code "158") (name "unconnected-(U19O-IO_L16P_36-PadG15)") (class "Default")
      (node (ref "U19") (pin "G15") (pinfunction "IO_L16P_36_G15") (pintype "bidirectional"))
    )
    (net (code "159") (name "unconnected-(U19O-IO_L17N_36-PadM15)") (class "Default")
      (node (ref "U19") (pin "M15") (pinfunction "IO_L17N_36_M15") (pintype "bidirectional"))
    )
    (net (code "160") (name "unconnected-(U19O-IO_L17P_36-PadM16)") (class "Default")
      (node (ref "U19") (pin "M16") (pinfunction "IO_L17P_36_M16") (pintype "bidirectional"))
    )
    (net (code "161") (name "unconnected-(U19O-IO_L18N_36-PadJ15)") (class "Default")
      (node (ref "U19") (pin "J15") (pinfunction "IO_L18N_36_J15") (pintype "bidirectional"))
    )
    (net (code "162") (name "unconnected-(U19O-IO_L18P_36-PadH15)") (class "Default")
      (node (ref "U19") (pin "H15") (pinfunction "IO_L18P_36_H15") (pintype "bidirectional"))
    )
    (net (code "163") (name "unconnected-(U27-NC-Pad6)") (class "Default")
      (node (ref "U27") (pin "6") (pinfunction "NC_6") (pintype "passive"))
    )
    (net (code "164") (name "unconnected-(U27-NC-Pad7)") (class "Default")
      (node (ref "U27") (pin "7") (pinfunction "NC_7") (pintype "passive"))
    )
  )
)
